# lightSoakV1-input-buffer-board-sch.net
KiCad netlist of a schematic drawn in Altium Designer
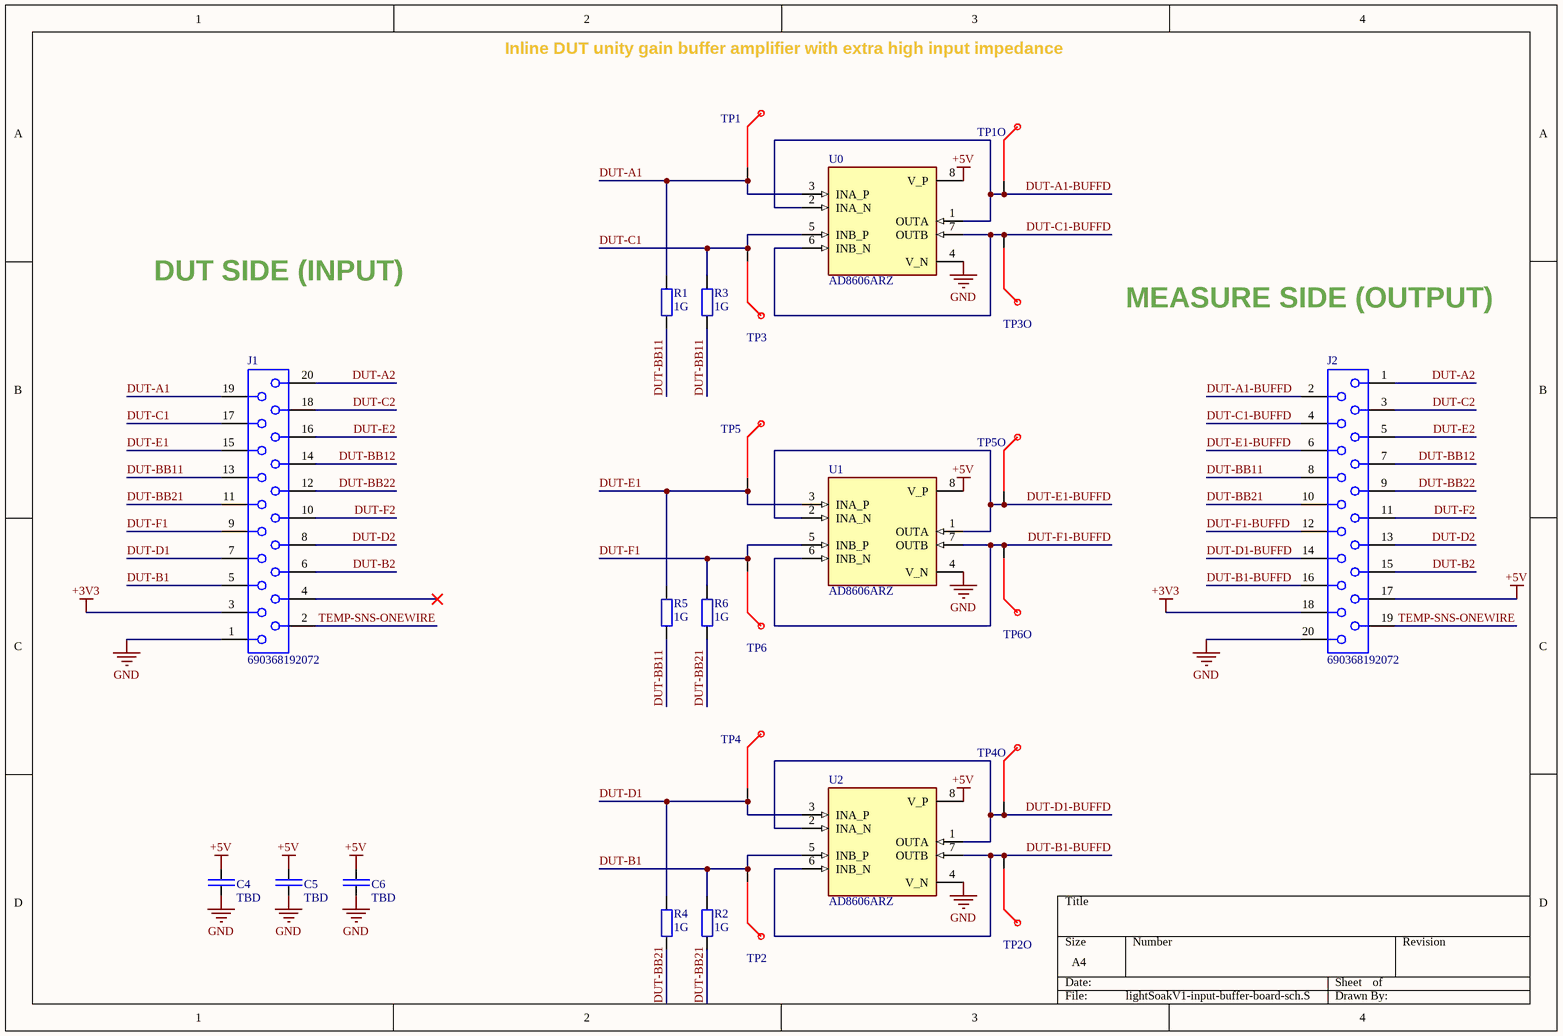
[diagram p0: lightSoakV1-input-buffer-board-sch.SchDoc]

(export (version "E")
  (design (tool "Eeschema 10.0.6"))
  (components
    (comp (ref "C4")
      (value "TBD")
      (footprint "Passives:FPR_0603_C_R0")
      (description "Capacitor - generic SMD")
      (fields (field (name "Comment") "C"))
      (libsource (lib "Passives") (part "C"))
    )
    (comp (ref "C5")
      (value "TBD")
      (footprint "Passives:FPR_0603_C_R0")
      (description "Capacitor - generic SMD")
      (fields (field (name "Comment") "C"))
      (libsource (lib "Passives") (part "C"))
    )
    (comp (ref "C6")
      (value "TBD")
      (footprint "Passives:FPR_0603_C_R0")
      (description "Capacitor - generic SMD")
      (fields (field (name "Comment") "C"))
      (libsource (lib "Passives") (part "C"))
    )
    (comp (ref "J1")
      (value "690368192072")
      (footprint "690368192072")
      (description "WR-MM Mini Module Connector, Female, THT, with Latch & Polarization, Angled, pitch 2.54mm, 20p")
      (fields (field (name "MANUFACTURER") "Wurth Elektronik"))
      (libsource (lib "Altium_WR-MM (rev22a)") (part "690368192072"))
    )
    (comp (ref "J2")
      (value "690368192072")
      (footprint "690368192072")
      (description "WR-MM Mini Module Connector, Female, THT, with Latch & Polarization, Angled, pitch 2.54mm, 20p")
      (fields (field (name "MANUFACTURER") "Wurth Elektronik"))
      (libsource (lib "Altium_WR-MM (rev22a)") (part "690368192072"))
    )
    (comp (ref "R1")
      (value "1G")
      (footprint "Passives:FPR_0805_R_R0")
      (description "Resistor - generic SMD")
      (fields (field (name "Comment") "R_1G"))
      (libsource (lib "Passives") (part "R"))
    )
    (comp (ref "R2")
      (value "1G")
      (footprint "Passives:FPR_0805_R_R0")
      (description "Resistor - generic SMD")
      (fields (field (name "Comment") "R_1G"))
      (libsource (lib "Passives") (part "R"))
    )
    (comp (ref "R3")
      (value "1G")
      (footprint "Passives:FPR_0805_R_R0")
      (description "Resistor - generic SMD")
      (fields (field (name "Comment") "R_1G"))
      (libsource (lib "Passives") (part "R"))
    )
    (comp (ref "R4")
      (value "1G")
      (footprint "Passives:FPR_0805_R_R0")
      (description "Resistor - generic SMD")
      (fields (field (name "Comment") "R_1G"))
      (libsource (lib "Passives") (part "R"))
    )
    (comp (ref "R5")
      (value "1G")
      (footprint "Passives:FPR_0805_R_R0")
      (description "Resistor - generic SMD")
      (fields (field (name "Comment") "R_1G"))
      (libsource (lib "Passives") (part "R"))
    )
    (comp (ref "R6")
      (value "1G")
      (footprint "Passives:FPR_0805_R_R0")
      (description "Resistor - generic SMD")
      (fields (field (name "Comment") "R_1G"))
      (libsource (lib "Passives") (part "R"))
    )
    (comp (ref "TP1")
      (value "Test Point")
      (footprint "Test Point 1.5mm SMD")
      (libsource (lib "planinsekLib_sch") (part "Test Point"))
    )
    (comp (ref "TP1O")
      (value "Test Point")
      (footprint "Test Point 1.5mm SMD")
      (libsource (lib "planinsekLib_sch") (part "Test Point"))
    )
    (comp (ref "TP2")
      (value "Test Point")
      (footprint "Test Point 1.5mm SMD")
      (libsource (lib "planinsekLib_sch") (part "Test Point"))
    )
    (comp (ref "TP2O")
      (value "Test Point")
      (footprint "Test Point 1.5mm SMD")
      (libsource (lib "planinsekLib_sch") (part "Test Point"))
    )
    (comp (ref "TP3")
      (value "Test Point")
      (footprint "Test Point 1.5mm SMD")
      (libsource (lib "planinsekLib_sch") (part "Test Point"))
    )
    (comp (ref "TP3O")
      (value "Test Point")
      (footprint "Test Point 1.5mm SMD")
      (libsource (lib "planinsekLib_sch") (part "Test Point"))
    )
    (comp (ref "TP4")
      (value "Test Point")
      (footprint "Test Point 1.5mm SMD")
      (libsource (lib "planinsekLib_sch") (part "Test Point"))
    )
    (comp (ref "TP4O")
      (value "Test Point")
      (footprint "Test Point 1.5mm SMD")
      (libsource (lib "planinsekLib_sch") (part "Test Point"))
    )
    (comp (ref "TP5")
      (value "Test Point")
      (footprint "Test Point 1.5mm SMD")
      (libsource (lib "planinsekLib_sch") (part "Test Point"))
    )
    (comp (ref "TP5O")
      (value "Test Point")
      (footprint "Test Point 1.5mm SMD")
      (libsource (lib "planinsekLib_sch") (part "Test Point"))
    )
    (comp (ref "TP6")
      (value "Test Point")
      (footprint "Test Point 1.5mm SMD")
      (libsource (lib "planinsekLib_sch") (part "Test Point"))
    )
    (comp (ref "TP6O")
      (value "Test Point")
      (footprint "Test Point 1.5mm SMD")
      (libsource (lib "planinsekLib_sch") (part "Test Point"))
    )
    (comp (ref "U0")
      (value "AD8606ARZ")
      (footprint "SOIC127P600X175-8N")
      (description "Dual rail to rail OP-AMP")
      (fields (field (name "MF") "Analog Devices"))
      (libsource (lib "AD8606ARZ") (part "AD8606ARZ"))
    )
    (comp (ref "U1")
      (value "AD8606ARZ")
      (footprint "SOIC127P600X175-8N")
      (description "Dual rail to rail OP-AMP")
      (fields (field (name "MF") "Analog Devices"))
      (libsource (lib "AD8606ARZ") (part "AD8606ARZ"))
    )
    (comp (ref "U2")
      (value "AD8606ARZ")
      (footprint "SOIC127P600X175-8N")
      (description "Dual rail to rail OP-AMP")
      (fields (field (name "MF") "Analog Devices"))
      (libsource (lib "AD8606ARZ") (part "AD8606ARZ"))
    )
  )
  (nets
    (net (code "1") (name "+3V3") (class "Default")
      (node (ref "J1") (pin "3") (pinfunction "3_3") (pintype "passive"))
      (node (ref "J2") (pin "18") (pinfunction "18_18") (pintype "passive"))
    )
    (net (code "2") (name "+5V") (class "Default")
      (node (ref "C4") (pin "2") (pinfunction "2_2") (pintype "passive"))
      (node (ref "C5") (pin "2") (pinfunction "2_2") (pintype "passive"))
      (node (ref "C6") (pin "2") (pinfunction "2_2") (pintype "passive"))
      (node (ref "J2") (pin "17") (pinfunction "17_17") (pintype "passive"))
      (node (ref "U0") (pin "8") (pinfunction "V_P_8") (pintype "power_in"))
      (node (ref "U1") (pin "8") (pinfunction "V_P_8") (pintype "power_in"))
      (node (ref "U2") (pin "8") (pinfunction "V_P_8") (pintype "power_in"))
    )
    (net (code "3") (name "/DUT-A1") (class "Default")
      (node (ref "J1") (pin "19") (pinfunction "19_19") (pintype "passive"))
      (node (ref "R1") (pin "2") (pinfunction "2_2") (pintype "passive"))
      (node (ref "TP1") (pin "1") (pintype "passive"))
      (node (ref "U0") (pin "3") (pinfunction "INA_P_3") (pintype "input"))
    )
    (net (code "4") (name "/DUT-A1-BUFFD") (class "Default")
      (node (ref "J2") (pin "2") (pinfunction "2_2") (pintype "passive"))
      (node (ref "TP1O") (pin "1") (pintype "passive"))
      (node (ref "U0") (pin "1") (pinfunction "OUTA_1") (pintype "input"))
      (node (ref "U0") (pin "2") (pinfunction "INA_N_2") (pintype "input"))
    )
    (net (code "5") (name "/DUT-A2") (class "Default")
      (node (ref "J1") (pin "20") (pinfunction "20_20") (pintype "passive"))
      (node (ref "J2") (pin "1") (pinfunction "1_1") (pintype "passive"))
    )
    (net (code "6") (name "/DUT-B1") (class "Default")
      (node (ref "J1") (pin "5") (pinfunction "5_5") (pintype "passive"))
      (node (ref "R2") (pin "2") (pinfunction "2_2") (pintype "passive"))
      (node (ref "TP2") (pin "1") (pintype "passive"))
      (node (ref "U2") (pin "5") (pinfunction "INB_P_5") (pintype "input"))
    )
    (net (code "7") (name "/DUT-B1-BUFFD") (class "Default")
      (node (ref "J2") (pin "16") (pinfunction "16_16") (pintype "passive"))
      (node (ref "TP2O") (pin "1") (pintype "passive"))
      (node (ref "U2") (pin "6") (pinfunction "INB_N_6") (pintype "input"))
      (node (ref "U2") (pin "7") (pinfunction "OUTB_7") (pintype "input"))
    )
    (net (code "8") (name "/DUT-B2") (class "Default")
      (node (ref "J1") (pin "6") (pinfunction "6_6") (pintype "passive"))
      (node (ref "J2") (pin "15") (pinfunction "15_15") (pintype "passive"))
    )
    (net (code "9") (name "/DUT-BB11") (class "Default")
      (node (ref "J1") (pin "13") (pinfunction "13_13") (pintype "passive"))
      (node (ref "J2") (pin "8") (pinfunction "8_8") (pintype "passive"))
      (node (ref "R1") (pin "1") (pinfunction "1_1") (pintype "passive"))
      (node (ref "R3") (pin "1") (pinfunction "1_1") (pintype "passive"))
      (node (ref "R5") (pin "1") (pinfunction "1_1") (pintype "passive"))
    )
    (net (code "10") (name "/DUT-BB12") (class "Default")
      (node (ref "J1") (pin "14") (pinfunction "14_14") (pintype "passive"))
      (node (ref "J2") (pin "7") (pinfunction "7_7") (pintype "passive"))
    )
    (net (code "11") (name "/DUT-BB21") (class "Default")
      (node (ref "J1") (pin "11") (pinfunction "11_11") (pintype "passive"))
      (node (ref "J2") (pin "10") (pinfunction "10_10") (pintype "passive"))
      (node (ref "R2") (pin "1") (pinfunction "1_1") (pintype "passive"))
      (node (ref "R4") (pin "1") (pinfunction "1_1") (pintype "passive"))
      (node (ref "R6") (pin "1") (pinfunction "1_1") (pintype "passive"))
    )
    (net (code "12") (name "/DUT-BB22") (class "Default")
      (node (ref "J1") (pin "12") (pinfunction "12_12") (pintype "passive"))
      (node (ref "J2") (pin "9") (pinfunction "9_9") (pintype "passive"))
    )
    (net (code "13") (name "/DUT-C1") (class "Default")
      (node (ref "J1") (pin "17") (pinfunction "17_17") (pintype "passive"))
      (node (ref "R3") (pin "2") (pinfunction "2_2") (pintype "passive"))
      (node (ref "TP3") (pin "1") (pintype "passive"))
      (node (ref "U0") (pin "5") (pinfunction "INB_P_5") (pintype "input"))
    )
    (net (code "14") (name "/DUT-C1-BUFFD") (class "Default")
      (node (ref "J2") (pin "4") (pinfunction "4_4") (pintype "passive"))
      (node (ref "TP3O") (pin "1") (pintype "passive"))
      (node (ref "U0") (pin "6") (pinfunction "INB_N_6") (pintype "input"))
      (node (ref "U0") (pin "7") (pinfunction "OUTB_7") (pintype "input"))
    )
    (net (code "15") (name "/DUT-C2") (class "Default")
      (node (ref "J1") (pin "18") (pinfunction "18_18") (pintype "passive"))
      (node (ref "J2") (pin "3") (pinfunction "3_3") (pintype "passive"))
    )
    (net (code "16") (name "/DUT-D1") (class "Default")
      (node (ref "J1") (pin "7") (pinfunction "7_7") (pintype "passive"))
      (node (ref "R4") (pin "2") (pinfunction "2_2") (pintype "passive"))
      (node (ref "TP4") (pin "1") (pintype "passive"))
      (node (ref "U2") (pin "3") (pinfunction "INA_P_3") (pintype "input"))
    )
    (net (code "17") (name "/DUT-D1-BUFFD") (class "Default")
      (node (ref "J2") (pin "14") (pinfunction "14_14") (pintype "passive"))
      (node (ref "TP4O") (pin "1") (pintype "passive"))
      (node (ref "U2") (pin "1") (pinfunction "OUTA_1") (pintype "input"))
      (node (ref "U2") (pin "2") (pinfunction "INA_N_2") (pintype "input"))
    )
    (net (code "18") (name "/DUT-D2") (class "Default")
      (node (ref "J1") (pin "8") (pinfunction "8_8") (pintype "passive"))
      (node (ref "J2") (pin "13") (pinfunction "13_13") (pintype "passive"))
    )
    (net (code "19") (name "/DUT-E1") (class "Default")
      (node (ref "J1") (pin "15") (pinfunction "15_15") (pintype "passive"))
      (node (ref "R5") (pin "2") (pinfunction "2_2") (pintype "passive"))
      (node (ref "TP5") (pin "1") (pintype "passive"))
      (node (ref "U1") (pin "3") (pinfunction "INA_P_3") (pintype "input"))
    )
    (net (code "20") (name "/DUT-E1-BUFFD") (class "Default")
      (node (ref "J2") (pin "6") (pinfunction "6_6") (pintype "passive"))
      (node (ref "TP5O") (pin "1") (pintype "passive"))
      (node (ref "U1") (pin "1") (pinfunction "OUTA_1") (pintype "input"))
      (node (ref "U1") (pin "2") (pinfunction "INA_N_2") (pintype "input"))
    )
    (net (code "21") (name "/DUT-E2") (class "Default")
      (node (ref "J1") (pin "16") (pinfunction "16_16") (pintype "passive"))
      (node (ref "J2") (pin "5") (pinfunction "5_5") (pintype "passive"))
    )
    (net (code "22") (name "/DUT-F1") (class "Default")
      (node (ref "J1") (pin "9") (pinfunction "9_9") (pintype "passive"))
      (node (ref "R6") (pin "2") (pinfunction "2_2") (pintype "passive"))
      (node (ref "TP6") (pin "1") (pintype "passive"))
      (node (ref "U1") (pin "5") (pinfunction "INB_P_5") (pintype "input"))
    )
    (net (code "23") (name "/DUT-F1-BUFFD") (class "Default")
      (node (ref "J2") (pin "12") (pinfunction "12_12") (pintype "passive"))
      (node (ref "TP6O") (pin "1") (pintype "passive"))
      (node (ref "U1") (pin "6") (pinfunction "INB_N_6") (pintype "input"))
      (node (ref "U1") (pin "7") (pinfunction "OUTB_7") (pintype "input"))
    )
    (net (code "24") (name "/DUT-F2") (class "Default")
      (node (ref "J1") (pin "10") (pinfunction "10_10") (pintype "passive"))
      (node (ref "J2") (pin "11") (pinfunction "11_11") (pintype "passive"))
    )
    (net (code "25") (name "/TEMP-SNS-ONEWIRE") (class "Default")
      (node (ref "J1") (pin "2") (pinfunction "2_2") (pintype "passive"))
      (node (ref "J2") (pin "19") (pinfunction "19_19") (pintype "passive"))
    )
    (net (code "26") (name "GND") (class "Default")
      (node (ref "C4") (pin "1") (pinfunction "1_1") (pintype "passive"))
      (node (ref "C5") (pin "1") (pinfunction "1_1") (pintype "passive"))
      (node (ref "C6") (pin "1") (pinfunction "1_1") (pintype "passive"))
      (node (ref "J1") (pin "1") (pinfunction "1_1") (pintype "passive"))
      (node (ref "J2") (pin "20") (pinfunction "20_20") (pintype "passive"))
      (node (ref "U0") (pin "4") (pinfunction "V_N_4") (pintype "power_in"))
      (node (ref "U1") (pin "4") (pinfunction "V_N_4") (pintype "power_in"))
      (node (ref "U2") (pin "4") (pinfunction "V_N_4") (pintype "power_in"))
    )
    (net (code "27") (name "unconnected-(J1-Pad4)") (class "Default")
      (node (ref "J1") (pin "4") (pinfunction "4_4") (pintype "passive+no_connect"))
    )
  )
)
